# VT_WRP.net
KiCad netlist of a schematic drawn in Altium Designer
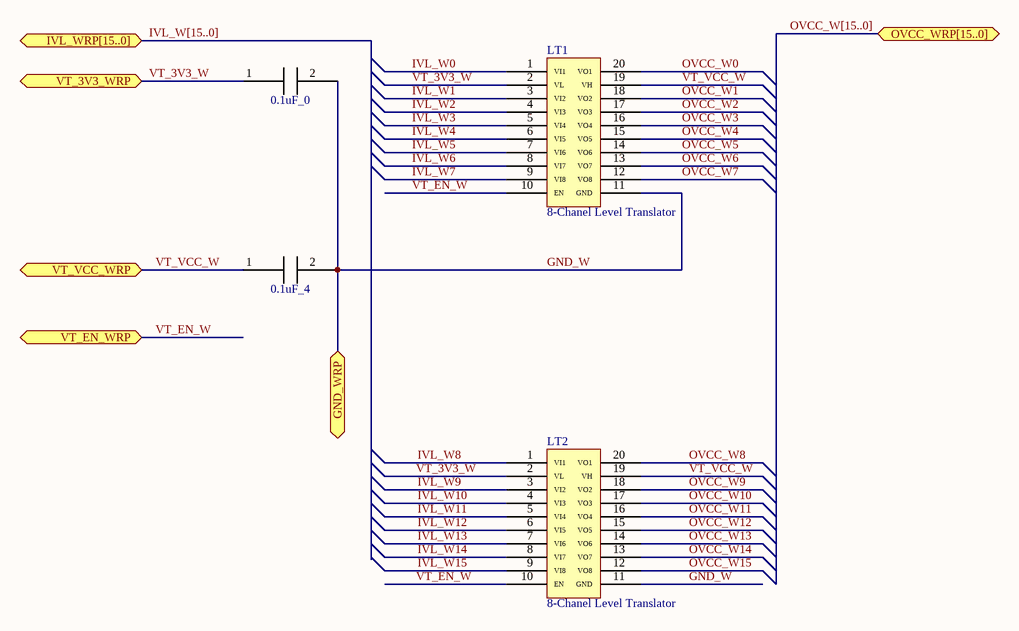
[diagram p0: VT_WRP.SchDoc]

(export (version "E")
  (design (tool "Eeschema 10.0.6"))
  (components
    (comp (ref "0.1uF_0")
      (value "0.1uF_0603")
      (footprint "0.1uF_0603")
      (libsource (lib "BBB_Board") (part "0.1uF_0603"))
    )
    (comp (ref "0.1uF_4")
      (value "0.1uF_0603")
      (footprint "0.1uF_0603")
      (libsource (lib "BBB_Board") (part "0.1uF_0603"))
    )
    (comp (ref "LT1")
      (value "8-Chanel Level Translator")
      (footprint "8-bit_level")
      (description "IC XLATR LEVEL BIDIR 8CH 20TSSOP")
      (fields
        (field (name "MANUFACTURER") "Maxim Integrated")
        (field (name "MANUFACTURER PART NUMBER") "MAX3008EUP+")
      )
      (libsource (lib "BBB_Board") (part "8-Chanel Level Translator"))
    )
    (comp (ref "LT2")
      (value "8-Chanel Level Translator")
      (footprint "8-bit_level")
      (description "IC XLATR LEVEL BIDIR 8CH 20TSSOP")
      (fields
        (field (name "MANUFACTURER") "Maxim Integrated")
        (field (name "MANUFACTURER PART NUMBER") "MAX3008EUP+")
      )
      (libsource (lib "BBB_Board") (part "8-Chanel Level Translator"))
    )
  )
  (nets
    (net (code "1") (name "/GND_W") (class "Default")
      (node (ref "0.1uF_0") (pin "2") (pinfunction "2_2") (pintype "passive"))
      (node (ref "0.1uF_4") (pin "2") (pinfunction "2_2") (pintype "passive"))
      (node (ref "LT1") (pin "11") (pinfunction "GND_11") (pintype "passive"))
      (node (ref "LT2") (pin "11") (pinfunction "GND_11") (pintype "passive"))
    )
    (net (code "2") (name "/IVL_W0") (class "Default")
      (node (ref "LT1") (pin "1") (pinfunction "VI1_1") (pintype "passive"))
    )
    (net (code "3") (name "/IVL_W1") (class "Default")
      (node (ref "LT1") (pin "3") (pinfunction "VI2_3") (pintype "passive"))
    )
    (net (code "4") (name "/IVL_W2") (class "Default")
      (node (ref "LT1") (pin "4") (pinfunction "VI3_4") (pintype "passive"))
    )
    (net (code "5") (name "/IVL_W3") (class "Default")
      (node (ref "LT1") (pin "5") (pinfunction "VI4_5") (pintype "passive"))
    )
    (net (code "6") (name "/IVL_W4") (class "Default")
      (node (ref "LT1") (pin "6") (pinfunction "VI5_6") (pintype "passive"))
    )
    (net (code "7") (name "/IVL_W5") (class "Default")
      (node (ref "LT1") (pin "7") (pinfunction "VI6_7") (pintype "passive"))
    )
    (net (code "8") (name "/IVL_W6") (class "Default")
      (node (ref "LT1") (pin "8") (pinfunction "VI7_8") (pintype "passive"))
    )
    (net (code "9") (name "/IVL_W7") (class "Default")
      (node (ref "LT1") (pin "9") (pinfunction "VI8_9") (pintype "passive"))
    )
    (net (code "10") (name "/IVL_W8") (class "Default")
      (node (ref "LT2") (pin "1") (pinfunction "VI1_1") (pintype "passive"))
    )
    (net (code "11") (name "/IVL_W9") (class "Default")
      (node (ref "LT2") (pin "3") (pinfunction "VI2_3") (pintype "passive"))
    )
    (net (code "12") (name "/IVL_W10") (class "Default")
      (node (ref "LT2") (pin "4") (pinfunction "VI3_4") (pintype "passive"))
    )
    (net (code "13") (name "/IVL_W11") (class "Default")
      (node (ref "LT2") (pin "5") (pinfunction "VI4_5") (pintype "passive"))
    )
    (net (code "14") (name "/IVL_W12") (class "Default")
      (node (ref "LT2") (pin "6") (pinfunction "VI5_6") (pintype "passive"))
    )
    (net (code "15") (name "/IVL_W13") (class "Default")
      (node (ref "LT2") (pin "7") (pinfunction "VI6_7") (pintype "passive"))
    )
    (net (code "16") (name "/IVL_W14") (class "Default")
      (node (ref "LT2") (pin "8") (pinfunction "VI7_8") (pintype "passive"))
    )
    (net (code "17") (name "/IVL_W15") (class "Default")
      (node (ref "LT2") (pin "9") (pinfunction "VI8_9") (pintype "passive"))
    )
    (net (code "19") (name "/OVCC_W0") (class "Default")
      (node (ref "LT1") (pin "20") (pinfunction "VO1_20") (pintype "passive"))
    )
    (net (code "20") (name "/OVCC_W1") (class "Default")
      (node (ref "LT1") (pin "18") (pinfunction "VO2_18") (pintype "passive"))
    )
    (net (code "21") (name "/OVCC_W2") (class "Default")
      (node (ref "LT1") (pin "17") (pinfunction "VO3_17") (pintype "passive"))
    )
    (net (code "22") (name "/OVCC_W3") (class "Default")
      (node (ref "LT1") (pin "16") (pinfunction "VO4_16") (pintype "passive"))
    )
    (net (code "23") (name "/OVCC_W4") (class "Default")
      (node (ref "LT1") (pin "15") (pinfunction "VO5_15") (pintype "passive"))
    )
    (net (code "24") (name "/OVCC_W5") (class "Default")
      (node (ref "LT1") (pin "14") (pinfunction "VO6_14") (pintype "passive"))
    )
    (net (code "25") (name "/OVCC_W6") (class "Default")
      (node (ref "LT1") (pin "13") (pinfunction "VO7_13") (pintype "passive"))
    )
    (net (code "26") (name "/OVCC_W7") (class "Default")
      (node (ref "LT1") (pin "12") (pinfunction "VO8_12") (pintype "passive"))
    )
    (net (code "27") (name "/OVCC_W8") (class "Default")
      (node (ref "LT2") (pin "20") (pinfunction "VO1_20") (pintype "passive"))
    )
    (net (code "28") (name "/OVCC_W9") (class "Default")
      (node (ref "LT2") (pin "18") (pinfunction "VO2_18") (pintype "passive"))
    )
    (net (code "29") (name "/OVCC_W10") (class "Default")
      (node (ref "LT2") (pin "17") (pinfunction "VO3_17") (pintype "passive"))
    )
    (net (code "30") (name "/OVCC_W11") (class "Default")
      (node (ref "LT2") (pin "16") (pinfunction "VO4_16") (pintype "passive"))
    )
    (net (code "31") (name "/OVCC_W12") (class "Default")
      (node (ref "LT2") (pin "15") (pinfunction "VO5_15") (pintype "passive"))
    )
    (net (code "32") (name "/OVCC_W13") (class "Default")
      (node (ref "LT2") (pin "14") (pinfunction "VO6_14") (pintype "passive"))
    )
    (net (code "33") (name "/OVCC_W14") (class "Default")
      (node (ref "LT2") (pin "13") (pinfunction "VO7_13") (pintype "passive"))
    )
    (net (code "34") (name "/OVCC_W15") (class "Default")
      (node (ref "LT2") (pin "12") (pinfunction "VO8_12") (pintype "passive"))
    )
    (net (code "36") (name "/VT_3V3_W") (class "Default")
      (node (ref "0.1uF_0") (pin "1") (pinfunction "1_1") (pintype "passive"))
      (node (ref "LT1") (pin "2") (pinfunction "VL_2") (pintype "passive"))
      (node (ref "LT2") (pin "2") (pinfunction "VL_2") (pintype "passive"))
    )
    (net (code "37") (name "/VT_EN_W") (class "Default")
      (node (ref "LT1") (pin "10") (pinfunction "EN_10") (pintype "passive"))
      (node (ref "LT2") (pin "10") (pinfunction "EN_10") (pintype "passive"))
    )
    (net (code "38") (name "/VT_VCC_W") (class "Default")
      (node (ref "0.1uF_4") (pin "1") (pinfunction "1_1") (pintype "passive"))
      (node (ref "LT1") (pin "19") (pinfunction "VH_19") (pintype "passive"))
      (node (ref "LT2") (pin "19") (pinfunction "VH_19") (pintype "passive"))
    )
  )
)
